# MC33797.net
KiCad netlist of a schematic drawn in Altium Designer
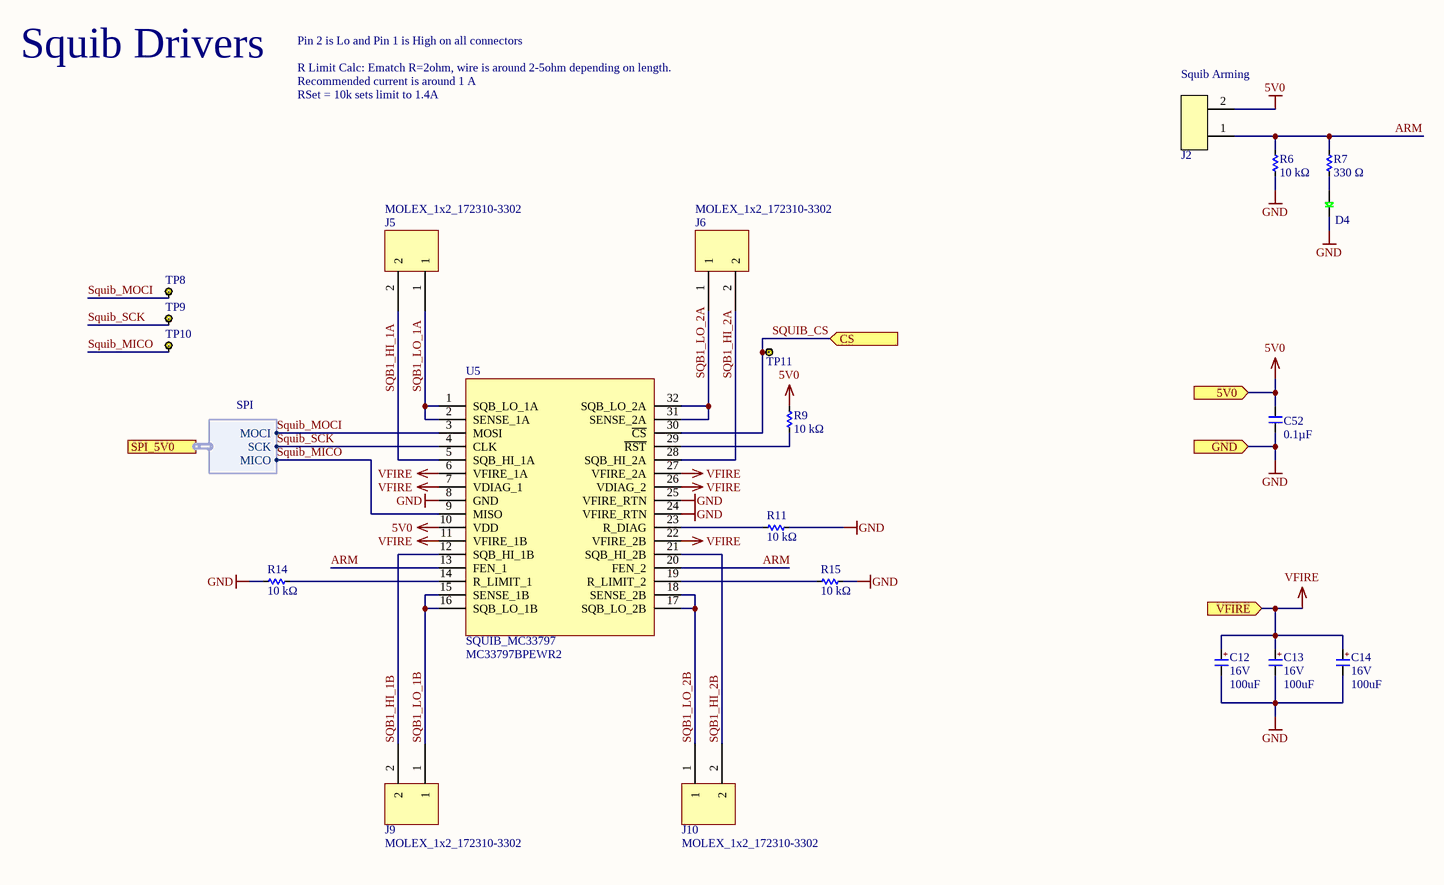
[diagram p0: MC33797.SchDoc]

(export (version "E")
  (design (tool "Eeschema 10.0.6"))
  (components
    (comp (ref "C12")
      (value "TPSC107M016R0200")
      (footprint "CAPCP6032X28N")
      (description "Cap Tant Solid 100uF 16V C CASE 20% (6 X 3.2 X 2.6mm) SMD 6032-28 0.2 Ohm 125°C T/R")
      (fields
        (field (name "CAPACITANCE") "100uF")
        (field (name "VOLTAGE RATING") "16V")
        (field (name "TOLERANCE") "20%")
      )
      (libsource (lib "Stanford Student Space Initiative") (part "CAP_TANT"))
    )
    (comp (ref "C13")
      (value "TPSC107M016R0200")
      (footprint "CAPCP6032X28N")
      (description "Cap Tant Solid 100uF 16V C CASE 20% (6 X 3.2 X 2.6mm) SMD 6032-28 0.2 Ohm 125°C T/R")
      (fields
        (field (name "CAPACITANCE") "100uF")
        (field (name "VOLTAGE RATING") "16V")
        (field (name "TOLERANCE") "20%")
      )
      (libsource (lib "Stanford Student Space Initiative") (part "CAP_TANT"))
    )
    (comp (ref "C14")
      (value "TPSC107M016R0200")
      (footprint "CAPCP6032X28N")
      (description "Cap Tant Solid 100uF 16V C CASE 20% (6 X 3.2 X 2.6mm) SMD 6032-28 0.2 Ohm 125°C T/R")
      (fields
        (field (name "CAPACITANCE") "100uF")
        (field (name "VOLTAGE RATING") "16V")
        (field (name "TOLERANCE") "20%")
      )
      (libsource (lib "Stanford Student Space Initiative") (part "CAP_TANT"))
    )
    (comp (ref "C52")
      (value "490-1519-1-ND")
      (footprint "C0603")
      (description "CAP CER 0603 0.1µF X7R 50V 10%")
      (fields
        (field (name "CAPACITANCE (SHORTHAND)") "0.1µF")
        (field (name "MANUFACTURER") "Murata Electronics North America")
      )
      (libsource (lib "Stanford Student Space Initiative") (part "__template_cap"))
    )
    (comp (ref "D4")
      (value "LED_C503B-GCS-CB0C0781")
      (footprint "LED_TH_5MM")
      (description "LED GREEN CLEAR 5MM ROUND T/H")
      (fields
        (field (name "MANUFACTURER") "Cree")
        (field (name "MANUFACTURER PART NUMBER") "C503B-GCS-CB0C0781")
      )
      (libsource (lib "Stanford Student Space Initiative") (part "LED_C503B-GCS-CB0C0781"))
    )
    (comp (ref "J2")
      (value "CONN_1x2")
      (footprint "CONN_1x2_100MIL")
      (description "CONN HEADER 2POS VERT T/H")
      (fields (field (name "MANUFACTURER PART NUMBER") "77311-118-02LF") (field (name "MANUFACTURER") "FCI"))
      (libsource (lib "Stanford Student Space Initiative") (part "Symbol"))
    )
    (comp (ref "J5")
      (value "MOLEX_1x2_172310-3302")
      (footprint "Molex 172310-xx02")
      (description "ULTRAFIT CONN HEADER R/A 2POS 3.5MM")
      (libsource (lib "") (part "MOLEX_1x2_1723101102_2"))
    )
    (comp (ref "J6")
      (value "MOLEX_1x2_172310-3302")
      (footprint "Molex 172310-xx02")
      (description "ULTRAFIT CONN HEADER R/A 2POS 3.5MM")
      (libsource (lib "") (part "MOLEX_1x2_1723101102_3"))
    )
    (comp (ref "J9")
      (value "MOLEX_1x2_172310-3302")
      (footprint "Molex 172310-xx02")
      (description "ULTRAFIT CONN HEADER R/A 2POS 3.5MM")
      (libsource (lib "") (part "MOLEX_1x2_1723101102_1"))
    )
    (comp (ref "J10")
      (value "MOLEX_1x2_172310-3302")
      (footprint "Molex 172310-xx02")
      (description "ULTRAFIT CONN HEADER R/A 2POS 3.5MM")
      (libsource (lib "Stanford Student Space Initiative") (part "MOLEX_1x2_1723101102"))
    )
    (comp (ref "R6")
      (value "311-10.0KHRCT-ND")
      (footprint "R0603")
      (description "RES SMD 10K OHM 1% 1/10W 0603")
      (fields
        (field (name "RESISTANCE") "10 kΩ")
        (field (name "MANUFACTURER PART NUMBER") "RC0603FR-0710KL")
        (field (name "MANUFACTURER") "Yageo")
      )
      (libsource (lib "Stanford Student Space Initiative") (part "__template_resistor"))
    )
    (comp (ref "R7")
      (value "311-330HRCT-ND")
      (footprint "R0603")
      (description "RES SMD 330 OHM 1% 1/10W 0603")
      (fields
        (field (name "RESISTANCE") "330 Ω")
        (field (name "MANUFACTURER PART NUMBER") "RC0603FR-07330RL")
        (field (name "MANUFACTURER") "Yageo")
      )
      (libsource (lib "Stanford Student Space Initiative") (part "__template_resistor"))
    )
    (comp (ref "R9")
      (value "311-10.0KHRCT-ND")
      (footprint "R0603")
      (description "RES SMD 10K OHM 1% 1/10W 0603")
      (fields
        (field (name "RESISTANCE") "10 kΩ")
        (field (name "MANUFACTURER PART NUMBER") "RC0603FR-0710KL")
        (field (name "MANUFACTURER") "Yageo")
      )
      (libsource (lib "Stanford Student Space Initiative") (part "__template_resistor"))
    )
    (comp (ref "R11")
      (value "311-10.0KHRCT-ND")
      (footprint "R0603")
      (description "RES SMD 10K OHM 1% 1/10W 0603")
      (fields
        (field (name "RESISTANCE") "10 kΩ")
        (field (name "MANUFACTURER PART NUMBER") "RC0603FR-0710KL")
        (field (name "MANUFACTURER") "Yageo")
      )
      (libsource (lib "Stanford Student Space Initiative") (part "__template_resistor"))
    )
    (comp (ref "R14")
      (value "311-10.0KHRCT-ND")
      (footprint "R0603")
      (description "RES SMD 10K OHM 1% 1/10W 0603")
      (fields
        (field (name "RESISTANCE") "10 kΩ")
        (field (name "MANUFACTURER PART NUMBER") "RC0603FR-0710KL")
        (field (name "MANUFACTURER") "Yageo")
      )
      (libsource (lib "Stanford Student Space Initiative") (part "__template_resistor"))
    )
    (comp (ref "R15")
      (value "311-10.0KHRCT-ND")
      (footprint "R0603")
      (description "RES SMD 10K OHM 1% 1/10W 0603")
      (fields
        (field (name "RESISTANCE") "10 kΩ")
        (field (name "MANUFACTURER PART NUMBER") "RC0603FR-0710KL")
        (field (name "MANUFACTURER") "Yageo")
      )
      (libsource (lib "Stanford Student Space Initiative") (part "__template_resistor"))
    )
    (comp (ref "TP8")
      (value "TEST_POINT_BLACK_KEYSTONE_5001")
      (footprint "TEST_POINT_BLACK_KEYSTONE_5001-Footprint-1")
      (description "BLACK T/H TEST POINT")
      (fields
        (field (name "MANUFACTURER PART NUMBER") "5001")
        (field (name "MANUFACTURER") "Keystone Electronics")
      )
      (libsource (lib "Stanford Student Space Initiative") (part "TEST_POINT_BLACK_KEYSTONE_5001"))
    )
    (comp (ref "TP9")
      (value "TEST_POINT_BLACK_KEYSTONE_5001")
      (footprint "TEST_POINT_BLACK_KEYSTONE_5001-Footprint-1")
      (description "BLACK T/H TEST POINT")
      (fields
        (field (name "MANUFACTURER PART NUMBER") "5001")
        (field (name "MANUFACTURER") "Keystone Electronics")
      )
      (libsource (lib "Stanford Student Space Initiative") (part "TEST_POINT_BLACK_KEYSTONE_5001"))
    )
    (comp (ref "TP10")
      (value "TEST_POINT_BLACK_KEYSTONE_5001")
      (footprint "TEST_POINT_BLACK_KEYSTONE_5001-Footprint-1")
      (description "BLACK T/H TEST POINT")
      (fields
        (field (name "MANUFACTURER PART NUMBER") "5001")
        (field (name "MANUFACTURER") "Keystone Electronics")
      )
      (libsource (lib "Stanford Student Space Initiative") (part "TEST_POINT_BLACK_KEYSTONE_5001"))
    )
    (comp (ref "TP11")
      (value "TEST_POINT_BLACK_KEYSTONE_5001")
      (footprint "TEST_POINT_BLACK_KEYSTONE_5001-Footprint-1")
      (description "BLACK T/H TEST POINT")
      (fields
        (field (name "MANUFACTURER PART NUMBER") "5001")
        (field (name "MANUFACTURER") "Keystone Electronics")
      )
      (libsource (lib "Stanford Student Space Initiative") (part "TEST_POINT_BLACK_KEYSTONE_5001"))
    )
    (comp (ref "U5")
      (value "SQUIB_MC33797")
      (footprint "SOT1762-1")
      (fields
        (field (name "MANUFACTURER") "NXP USA Inc.")
        (field (name "MANUFACTURER PART NUMBER") "MC33797BPEWR2")
      )
      (libsource (lib "Stanford Student Space Initiative") (part "SQUIB_MC33797"))
    )
  )
  (nets
    (net (code "2") (name "/ARM") (class "Default")
      (node (ref "J2") (pin "1") (pinfunction "1_1") (pintype "passive"))
      (node (ref "R6") (pin "1") (pinfunction "1_1") (pintype "passive"))
      (node (ref "R7") (pin "2") (pinfunction "2_2") (pintype "passive"))
      (node (ref "U5") (pin "13") (pinfunction "FEN_1_13") (pintype "passive"))
      (node (ref "U5") (pin "20") (pinfunction "FEN_2_20") (pintype "passive"))
    )
    (net (code "3") (name "/SQB1_HI_1A") (class "Default")
      (node (ref "J5") (pin "2") (pinfunction "2_2") (pintype "passive"))
      (node (ref "U5") (pin "5") (pinfunction "SQB_HI_1A_5") (pintype "passive"))
    )
    (net (code "4") (name "/SQB1_HI_1B") (class "Default")
      (node (ref "J9") (pin "2") (pinfunction "2_2") (pintype "passive"))
      (node (ref "U5") (pin "12") (pinfunction "SQB_HI_1B_12") (pintype "passive"))
    )
    (net (code "5") (name "/SQB1_HI_2A") (class "Default")
      (node (ref "J6") (pin "2") (pinfunction "2_2") (pintype "passive"))
      (node (ref "U5") (pin "28") (pinfunction "SQB_HI_2A_28") (pintype "passive"))
    )
    (net (code "6") (name "/SQB1_HI_2B") (class "Default")
      (node (ref "J10") (pin "2") (pinfunction "2_2") (pintype "passive"))
      (node (ref "U5") (pin "21") (pinfunction "SQB_HI_2B_21") (pintype "passive"))
    )
    (net (code "7") (name "/SQB1_LO_1A") (class "Default")
      (node (ref "J5") (pin "1") (pinfunction "1_1") (pintype "passive"))
      (node (ref "U5") (pin "1") (pinfunction "SQB_LO_1A_1") (pintype "passive"))
      (node (ref "U5") (pin "2") (pinfunction "SENSE_1A_2") (pintype "passive"))
    )
    (net (code "8") (name "/SQB1_LO_1B") (class "Default")
      (node (ref "J9") (pin "1") (pinfunction "1_1") (pintype "passive"))
      (node (ref "U5") (pin "15") (pinfunction "SENSE_1B_15") (pintype "passive"))
      (node (ref "U5") (pin "16") (pinfunction "SQB_LO_1B_16") (pintype "passive"))
    )
    (net (code "9") (name "/SQB1_LO_2A") (class "Default")
      (node (ref "J6") (pin "1") (pinfunction "1_1") (pintype "passive"))
      (node (ref "U5") (pin "31") (pinfunction "SENSE_2A_31") (pintype "passive"))
      (node (ref "U5") (pin "32") (pinfunction "SQB_LO_2A_32") (pintype "passive"))
    )
    (net (code "10") (name "/SQB1_LO_2B") (class "Default")
      (node (ref "J10") (pin "1") (pinfunction "1_1") (pintype "passive"))
      (node (ref "U5") (pin "17") (pinfunction "SQB_LO_2B_17") (pintype "passive"))
      (node (ref "U5") (pin "18") (pinfunction "SENSE_2B_18") (pintype "passive"))
    )
    (net (code "11") (name "/SQUIB_CS") (class "Default")
      (node (ref "TP11") (pin "1") (pinfunction "1_1") (pintype "passive"))
      (node (ref "U5") (pin "30") (pinfunction "~{CS}_30") (pintype "passive"))
    )
    (net (code "12") (name "/Squib_MICO") (class "Default")
      (node (ref "TP10") (pin "1") (pinfunction "1_1") (pintype "passive"))
      (node (ref "U5") (pin "9") (pinfunction "MISO_9") (pintype "passive"))
    )
    (net (code "13") (name "/Squib_MOCI") (class "Default")
      (node (ref "TP8") (pin "1") (pinfunction "1_1") (pintype "passive"))
      (node (ref "U5") (pin "3") (pinfunction "MOSI_3") (pintype "passive"))
    )
    (net (code "14") (name "/Squib_SCK") (class "Default")
      (node (ref "TP9") (pin "1") (pinfunction "1_1") (pintype "passive"))
      (node (ref "U5") (pin "4") (pinfunction "CLK_4") (pintype "passive"))
    )
    (net (code "16") (name "5V0") (class "Default")
      (node (ref "C52") (pin "1") (pintype "passive"))
      (node (ref "J2") (pin "2") (pinfunction "2_2") (pintype "passive"))
      (node (ref "R9") (pin "2") (pinfunction "2_2") (pintype "passive"))
      (node (ref "U5") (pin "10") (pinfunction "VDD_10") (pintype "passive"))
    )
    (net (code "17") (name "GND") (class "Default")
      (node (ref "C12") (pin "2") (pinfunction "K_2") (pintype "passive"))
      (node (ref "C13") (pin "2") (pinfunction "K_2") (pintype "passive"))
      (node (ref "C14") (pin "2") (pinfunction "K_2") (pintype "passive"))
      (node (ref "C52") (pin "2") (pintype "passive"))
      (node (ref "D4") (pin "2") (pinfunction "K_2") (pintype "passive"))
      (node (ref "R11") (pin "2") (pinfunction "2_2") (pintype "passive"))
      (node (ref "R14") (pin "1") (pinfunction "1_1") (pintype "passive"))
      (node (ref "R15") (pin "2") (pinfunction "2_2") (pintype "passive"))
      (node (ref "R6") (pin "2") (pinfunction "2_2") (pintype "passive"))
      (node (ref "U5") (pin "24") (pinfunction "VFIRE_RTN_24") (pintype "passive"))
      (node (ref "U5") (pin "25") (pinfunction "VFIRE_RTN_25") (pintype "passive"))
      (node (ref "U5") (pin "8") (pinfunction "GND_8") (pintype "passive"))
    )
    (net (code "18") (name "Net-(D4-A)") (class "Default")
      (node (ref "D4") (pin "1") (pinfunction "A_1") (pintype "passive"))
      (node (ref "R7") (pin "1") (pinfunction "1_1") (pintype "passive"))
    )
    (net (code "19") (name "Net-(U5-R_DIAG)") (class "Default")
      (node (ref "R11") (pin "1") (pinfunction "1_1") (pintype "passive"))
      (node (ref "U5") (pin "23") (pinfunction "R_DIAG_23") (pintype "passive"))
    )
    (net (code "20") (name "Net-(U5-R_LIMIT_1)") (class "Default")
      (node (ref "R14") (pin "2") (pinfunction "2_2") (pintype "passive"))
      (node (ref "U5") (pin "14") (pinfunction "R_LIMIT_1_14") (pintype "passive"))
    )
    (net (code "21") (name "Net-(U5-R_LIMIT_2)") (class "Default")
      (node (ref "R15") (pin "1") (pinfunction "1_1") (pintype "passive"))
      (node (ref "U5") (pin "19") (pinfunction "R_LIMIT_2_19") (pintype "passive"))
    )
    (net (code "22") (name "Net-(U5-~{RST})") (class "Default")
      (node (ref "R9") (pin "1") (pinfunction "1_1") (pintype "passive"))
      (node (ref "U5") (pin "29") (pinfunction "~{RST}_29") (pintype "passive"))
    )
    (net (code "23") (name "VFIRE") (class "Default")
      (node (ref "C12") (pin "1") (pinfunction "A_1") (pintype "passive"))
      (node (ref "C13") (pin "1") (pinfunction "A_1") (pintype "passive"))
      (node (ref "C14") (pin "1") (pinfunction "A_1") (pintype "passive"))
      (node (ref "U5") (pin "11") (pinfunction "VFIRE_1B_11") (pintype "passive"))
      (node (ref "U5") (pin "22") (pinfunction "VFIRE_2B_22") (pintype "passive"))
      (node (ref "U5") (pin "26") (pinfunction "VDIAG_2_26") (pintype "passive"))
      (node (ref "U5") (pin "27") (pinfunction "VFIRE_2A_27") (pintype "passive"))
      (node (ref "U5") (pin "6") (pinfunction "VFIRE_1A_6") (pintype "passive"))
      (node (ref "U5") (pin "7") (pinfunction "VDIAG_1_7") (pintype "passive"))
    )
  )
)
